# as5040.net
KiCad netlist of a schematic drawn in EAGLE
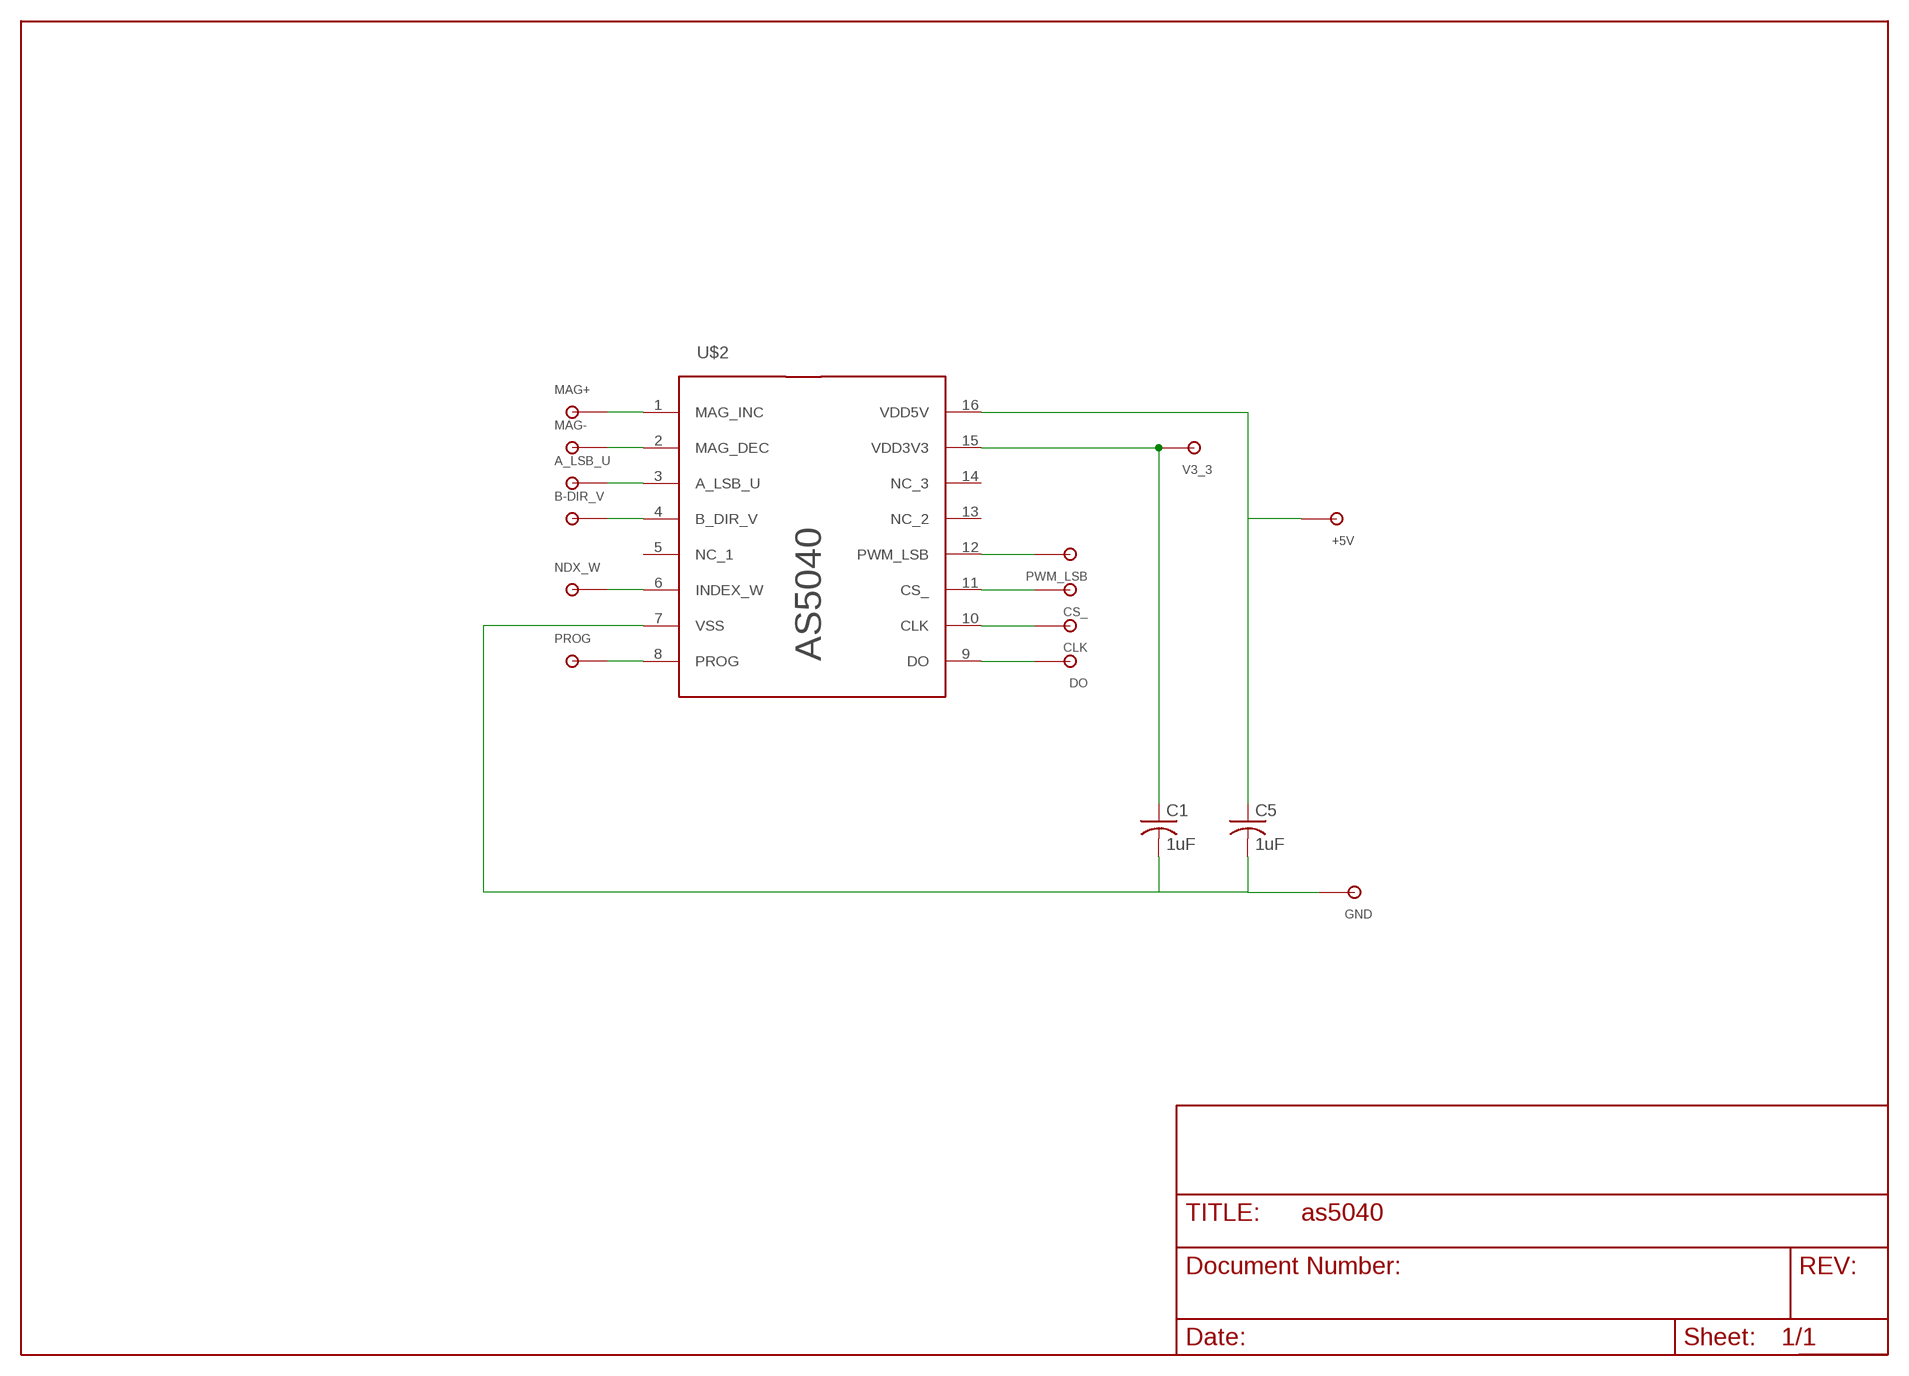
[diagram p0: schematic, sheet 1]

(export (version "E")
  (design (tool "Eeschema 10.0.6"))
  (components
    (comp (ref "+5V")
      (value "TPSOL")
      (footprint "eagle-import:TP_SOL")
      (libsource (lib "eagle-import") (part "TPSOL"))
    )
    (comp (ref "A_LSB_U")
      (value "TPSOL")
      (footprint "eagle-import:TP_SOL")
      (libsource (lib "eagle-import") (part "TPSOL"))
    )
    (comp (ref "B-DIR_V")
      (value "TPSOL")
      (footprint "eagle-import:TP_SOL")
      (libsource (lib "eagle-import") (part "TPSOL"))
    )
    (comp (ref "C1")
      (value "1uF")
      (footprint "eagle-import:C0805K")
      (libsource (lib "eagle-import") (part "C-USC0805K"))
    )
    (comp (ref "C5")
      (value "1uF")
      (footprint "eagle-import:C0805K")
      (libsource (lib "eagle-import") (part "C-USC0805K"))
    )
    (comp (ref "CLK")
      (value "TPSOL")
      (footprint "eagle-import:TP_SOL")
      (libsource (lib "eagle-import") (part "TPSOL"))
    )
    (comp (ref "CS_")
      (value "TPSOL")
      (footprint "eagle-import:TP_SOL")
      (libsource (lib "eagle-import") (part "TPSOL"))
    )
    (comp (ref "DO")
      (value "TPSOL")
      (footprint "eagle-import:TP_SOL")
      (libsource (lib "eagle-import") (part "TPSOL"))
    )
    (comp (ref "GND")
      (value "TPSOL")
      (footprint "eagle-import:TP_SOL")
      (libsource (lib "eagle-import") (part "TPSOL"))
    )
    (comp (ref "MAG+")
      (value "TPSOL")
      (footprint "eagle-import:TP_SOL")
      (libsource (lib "eagle-import") (part "TPSOL"))
    )
    (comp (ref "MAG-")
      (value "TPSOL")
      (footprint "eagle-import:TP_SOL")
      (libsource (lib "eagle-import") (part "TPSOL"))
    )
    (comp (ref "NDX_W")
      (value "TPSOL")
      (footprint "eagle-import:TP_SOL")
      (libsource (lib "eagle-import") (part "TPSOL"))
    )
    (comp (ref "PROG")
      (value "TPSOL")
      (footprint "eagle-import:TP_SOL")
      (libsource (lib "eagle-import") (part "TPSOL"))
    )
    (comp (ref "PWM_LSB")
      (value "TPSOL")
      (footprint "eagle-import:TP_SOL")
      (libsource (lib "eagle-import") (part "TPSOL"))
    )
    (comp (ref "U$2")
      (value "AS5040")
      (footprint "eagle-import:TSSOP16")
      (libsource (lib "eagle-import") (part "AS5040"))
    )
    (comp (ref "V3_3")
      (value "TPSOL")
      (footprint "eagle-import:TP_SOL")
      (libsource (lib "eagle-import") (part "TPSOL"))
    )
  )
  (nets
    (net (code "1") (name "Net-(U$2-A_LSB_U)") (class "Default")
      (node (ref "A_LSB_U") (pin "P$1") (pinfunction "P$1_P$1") (pintype "bidirectional"))
      (node (ref "U$2") (pin "3") (pinfunction "A_LSB_U_3") (pintype "bidirectional"))
    )
    (net (code "2") (name "Net-(U$2-B_DIR_V)") (class "Default")
      (node (ref "B-DIR_V") (pin "P$1") (pinfunction "P$1_P$1") (pintype "bidirectional"))
      (node (ref "U$2") (pin "4") (pinfunction "B_DIR_V_4") (pintype "bidirectional"))
    )
    (net (code "3") (name "Net-(U$2-CLK)") (class "Default")
      (node (ref "CLK") (pin "P$1") (pinfunction "P$1_P$1") (pintype "bidirectional"))
      (node (ref "U$2") (pin "10") (pinfunction "CLK_10") (pintype "bidirectional"))
    )
    (net (code "4") (name "Net-(U$2-CS_)") (class "Default")
      (node (ref "CS_") (pin "P$1") (pinfunction "P$1_P$1") (pintype "bidirectional"))
      (node (ref "U$2") (pin "11") (pinfunction "CS__11") (pintype "bidirectional"))
    )
    (net (code "5") (name "Net-(U$2-DO)") (class "Default")
      (node (ref "DO") (pin "P$1") (pinfunction "P$1_P$1") (pintype "bidirectional"))
      (node (ref "U$2") (pin "9") (pinfunction "DO_9") (pintype "bidirectional"))
    )
    (net (code "6") (name "Net-(U$2-INDEX_W)") (class "Default")
      (node (ref "NDX_W") (pin "P$1") (pinfunction "P$1_P$1") (pintype "bidirectional"))
      (node (ref "U$2") (pin "6") (pinfunction "INDEX_W_6") (pintype "bidirectional"))
    )
    (net (code "7") (name "Net-(U$2-MAG_DEC)") (class "Default")
      (node (ref "MAG-") (pin "P$1") (pinfunction "P$1_P$1") (pintype "bidirectional"))
      (node (ref "U$2") (pin "2") (pinfunction "MAG_DEC_2") (pintype "bidirectional"))
    )
    (net (code "8") (name "Net-(U$2-MAG_INC)") (class "Default")
      (node (ref "MAG+") (pin "P$1") (pinfunction "P$1_P$1") (pintype "bidirectional"))
      (node (ref "U$2") (pin "1") (pinfunction "MAG_INC_1") (pintype "bidirectional"))
    )
    (net (code "9") (name "Net-(U$2-PROG)") (class "Default")
      (node (ref "PROG") (pin "P$1") (pinfunction "P$1_P$1") (pintype "bidirectional"))
      (node (ref "U$2") (pin "8") (pinfunction "PROG_8") (pintype "bidirectional"))
    )
    (net (code "10") (name "Net-(U$2-PWM_LSB)") (class "Default")
      (node (ref "PWM_LSB") (pin "P$1") (pinfunction "P$1_P$1") (pintype "bidirectional"))
      (node (ref "U$2") (pin "12") (pinfunction "PWM_LSB_12") (pintype "bidirectional"))
    )
    (net (code "11") (name "Net-(U$2-VDD3V3)") (class "Default")
      (node (ref "C1") (pin "1") (pinfunction "1_1") (pintype "passive"))
      (node (ref "U$2") (pin "15") (pinfunction "VDD3V3_15") (pintype "bidirectional"))
      (node (ref "V3_3") (pin "P$1") (pinfunction "P$1_P$1") (pintype "bidirectional"))
    )
    (net (code "12") (name "Net-(U$2-VDD5V)") (class "Default")
      (node (ref "+5V") (pin "P$1") (pinfunction "P$1_P$1") (pintype "bidirectional"))
      (node (ref "C5") (pin "1") (pinfunction "1_1") (pintype "passive"))
      (node (ref "U$2") (pin "16") (pinfunction "VDD5V_16") (pintype "bidirectional"))
    )
    (net (code "13") (name "Net-(U$2-VSS)") (class "Default")
      (node (ref "C1") (pin "2") (pinfunction "2_2") (pintype "passive"))
      (node (ref "C5") (pin "2") (pinfunction "2_2") (pintype "passive"))
      (node (ref "GND") (pin "P$1") (pinfunction "P$1_P$1") (pintype "bidirectional"))
      (node (ref "U$2") (pin "7") (pinfunction "VSS_7") (pintype "bidirectional"))
    )
    (net (code "14") (name "unconnected-(U$2-NC_1-Pad5)") (class "Default")
      (node (ref "U$2") (pin "5") (pinfunction "NC_1_5") (pintype "bidirectional"))
    )
    (net (code "15") (name "unconnected-(U$2-NC_2-Pad13)") (class "Default")
      (node (ref "U$2") (pin "13") (pinfunction "NC_2_13") (pintype "bidirectional"))
    )
    (net (code "16") (name "unconnected-(U$2-NC_3-Pad14)") (class "Default")
      (node (ref "U$2") (pin "14") (pinfunction "NC_3_14") (pintype "bidirectional"))
    )
  )
)
